# S02_Power_Converters.net
KiCad netlist of a schematic drawn in Altium Designer
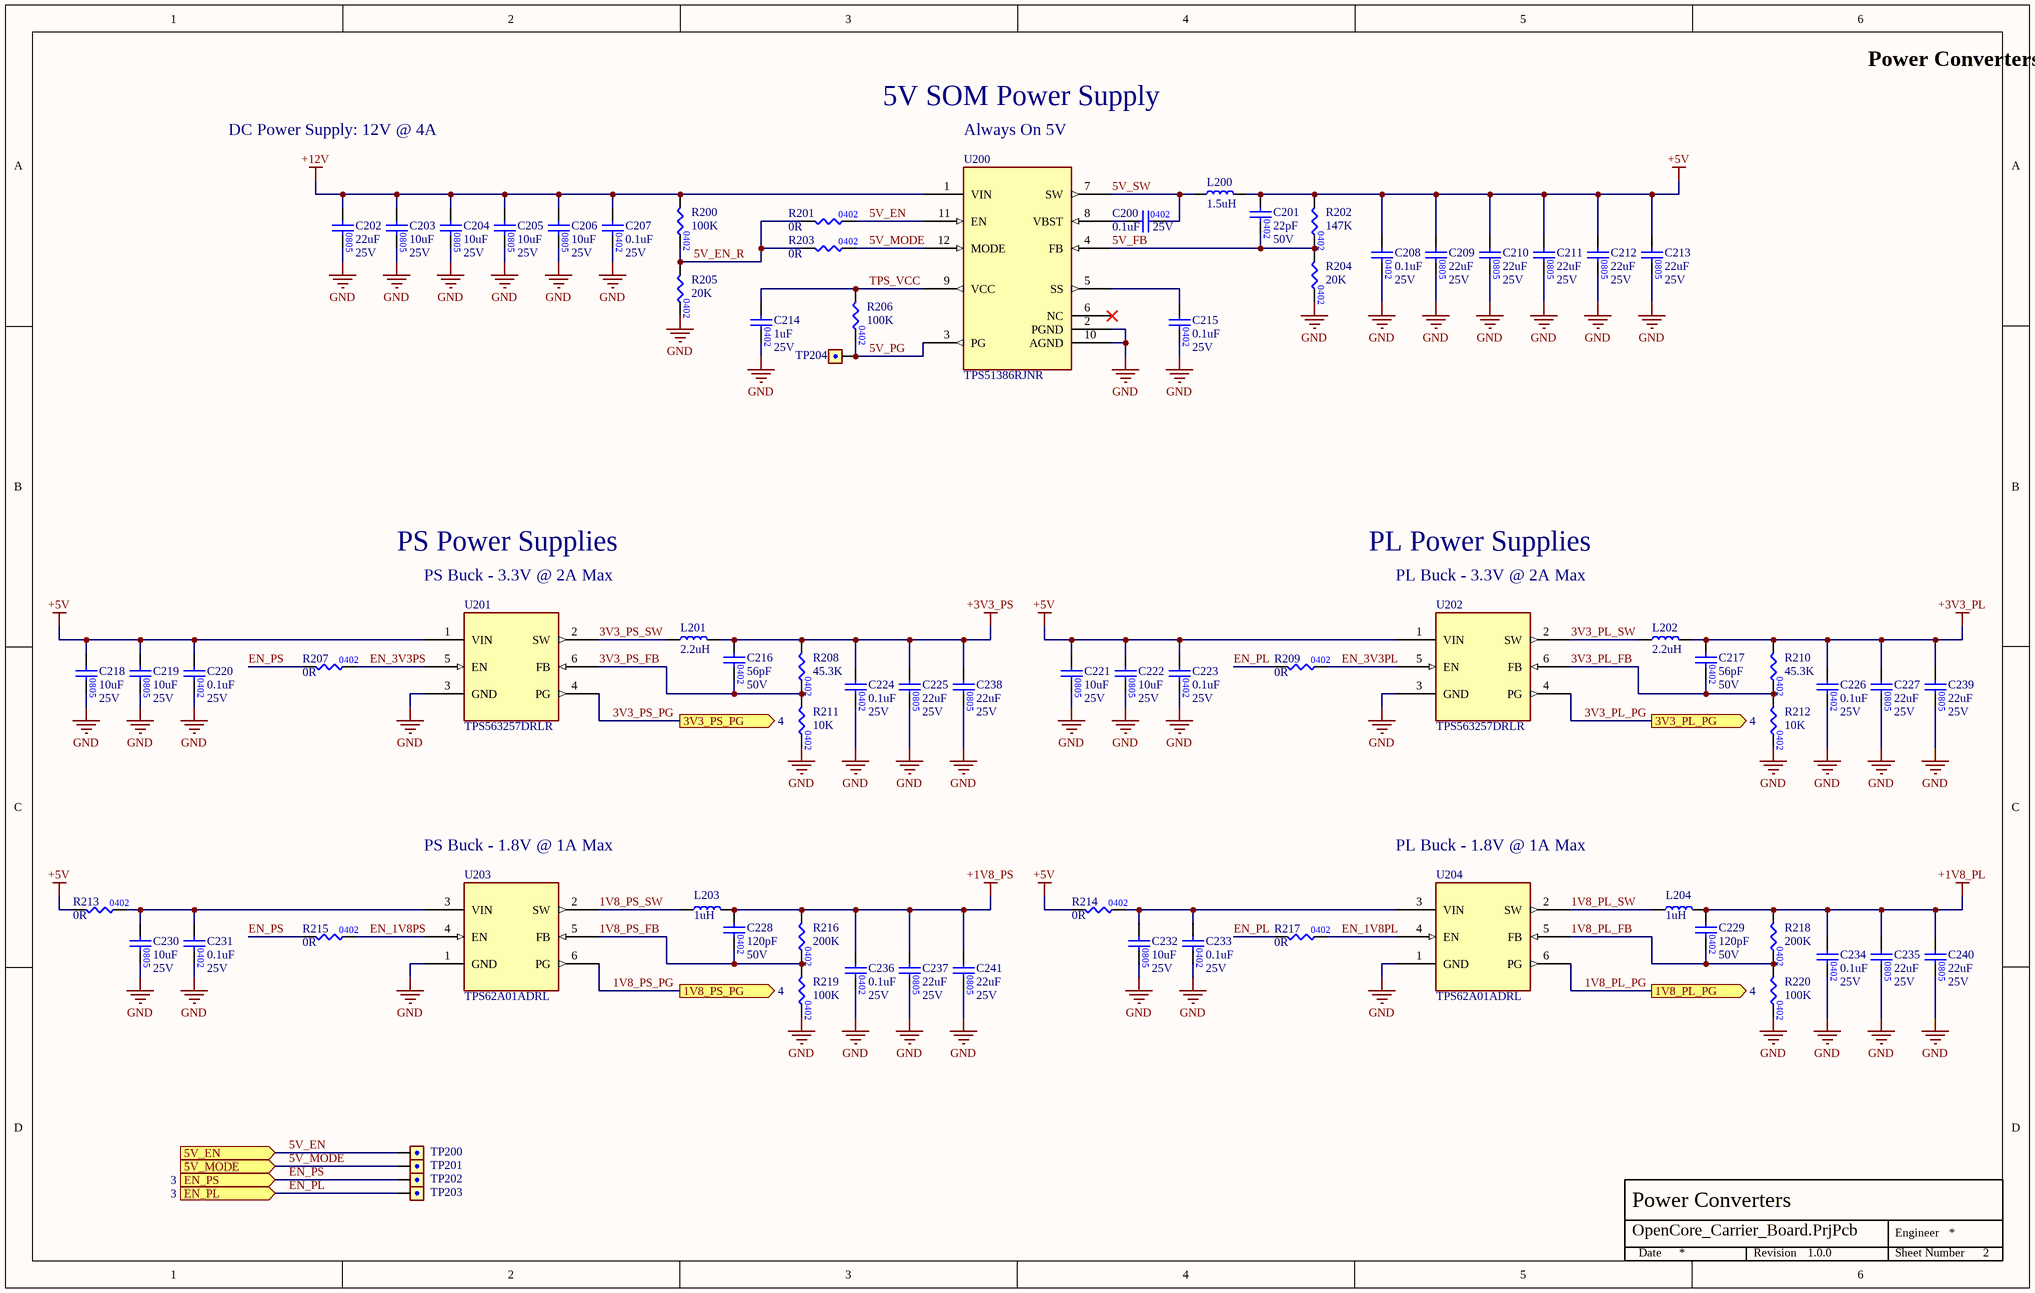
[diagram p0: S02_Power_Converters.SchDoc]

(export (version "E")
  (design (tool "Eeschema 10.0.6"))
  (components
    (comp (ref "C200")
      (value "0.1uF")
      (footprint "CAP0402")
      (description "CAP CER 0.1UF 25V X5R 0402")
      (fields
        (field (name "MANUFACTURER") "Samsung Electro-Mechanics")
        (field (name "TOLERANCE") "10%")
        (field (name "VOLTAGE RATING") "25V")
      )
      (libsource (lib "OpenCore_Sch_Lib") (part "CAP_CL05A104KA5NNNC"))
    )
    (comp (ref "C201")
      (value "22pF")
      (footprint "CAP0402")
      (description "CAP CER 22PF 50V C0G/NP0 0402")
      (fields
        (field (name "MANUFACTURER") "Samsung Electro-Mechanics")
        (field (name "TOLERANCE") "5%")
        (field (name "VOLTAGE RATING") "50V")
      )
      (libsource (lib "OpenCore_Sch_Lib") (part "CAP_CL05C220JB51PNC"))
    )
    (comp (ref "C202")
      (value "22uF")
      (footprint "CAP0805")
      (description "CAP CER 22UF 25V X5R 0805")
      (fields
        (field (name "MANUFACTURER") "Samsung Electro-Mechanics")
        (field (name "TOLERANCE") "20%")
        (field (name "VOLTAGE RATING") "25V")
      )
      (libsource (lib "OpenCore_Sch_Lib") (part "CAP_CL21A226MAYNNNE"))
    )
    (comp (ref "C203")
      (value "10uF")
      (footprint "CAP0805")
      (description "CAP CER 10UF 25V X5R 0805")
      (fields
        (field (name "MANUFACTURER") "Samsung Electro-Mechanics")
        (field (name "TOLERANCE") "10%")
        (field (name "VOLTAGE RATING") "25V")
      )
      (libsource (lib "OpenCore_Sch_Lib") (part "CAP_CL21A106KAYNNNE"))
    )
    (comp (ref "C204")
      (value "10uF")
      (footprint "CAP0805")
      (description "CAP CER 10UF 25V X5R 0805")
      (fields
        (field (name "MANUFACTURER") "Samsung Electro-Mechanics")
        (field (name "TOLERANCE") "10%")
        (field (name "VOLTAGE RATING") "25V")
      )
      (libsource (lib "OpenCore_Sch_Lib") (part "CAP_CL21A106KAYNNNE"))
    )
    (comp (ref "C205")
      (value "10uF")
      (footprint "CAP0805")
      (description "CAP CER 10UF 25V X5R 0805")
      (fields
        (field (name "MANUFACTURER") "Samsung Electro-Mechanics")
        (field (name "TOLERANCE") "10%")
        (field (name "VOLTAGE RATING") "25V")
      )
      (libsource (lib "OpenCore_Sch_Lib") (part "CAP_CL21A106KAYNNNE"))
    )
    (comp (ref "C206")
      (value "10uF")
      (footprint "CAP0805")
      (description "CAP CER 10UF 25V X5R 0805")
      (fields
        (field (name "MANUFACTURER") "Samsung Electro-Mechanics")
        (field (name "TOLERANCE") "10%")
        (field (name "VOLTAGE RATING") "25V")
      )
      (libsource (lib "OpenCore_Sch_Lib") (part "CAP_CL21A106KAYNNNE"))
    )
    (comp (ref "C207")
      (value "0.1uF")
      (footprint "CAP0402")
      (description "CAP CER 0.1UF 25V X5R 0402")
      (fields
        (field (name "MANUFACTURER") "Samsung Electro-Mechanics")
        (field (name "TOLERANCE") "10%")
        (field (name "VOLTAGE RATING") "25V")
      )
      (libsource (lib "OpenCore_Sch_Lib") (part "CAP_CL05A104KA5NNNC"))
    )
    (comp (ref "C208")
      (value "0.1uF")
      (footprint "CAP0402")
      (description "CAP CER 0.1UF 25V X5R 0402")
      (fields
        (field (name "MANUFACTURER") "Samsung Electro-Mechanics")
        (field (name "TOLERANCE") "10%")
        (field (name "VOLTAGE RATING") "25V")
      )
      (libsource (lib "OpenCore_Sch_Lib") (part "CAP_CL05A104KA5NNNC"))
    )
    (comp (ref "C209")
      (value "22uF")
      (footprint "CAP0805")
      (description "CAP CER 22UF 25V X5R 0805")
      (fields
        (field (name "MANUFACTURER") "Samsung Electro-Mechanics")
        (field (name "TOLERANCE") "20%")
        (field (name "VOLTAGE RATING") "25V")
      )
      (libsource (lib "OpenCore_Sch_Lib") (part "CAP_CL21A226MAYNNNE"))
    )
    (comp (ref "C210")
      (value "22uF")
      (footprint "CAP0805")
      (description "CAP CER 22UF 25V X5R 0805")
      (fields
        (field (name "MANUFACTURER") "Samsung Electro-Mechanics")
        (field (name "TOLERANCE") "20%")
        (field (name "VOLTAGE RATING") "25V")
      )
      (libsource (lib "OpenCore_Sch_Lib") (part "CAP_CL21A226MAYNNNE"))
    )
    (comp (ref "C211")
      (value "22uF")
      (footprint "CAP0805")
      (description "CAP CER 22UF 25V X5R 0805")
      (fields
        (field (name "MANUFACTURER") "Samsung Electro-Mechanics")
        (field (name "TOLERANCE") "20%")
        (field (name "VOLTAGE RATING") "25V")
      )
      (libsource (lib "OpenCore_Sch_Lib") (part "CAP_CL21A226MAYNNNE"))
    )
    (comp (ref "C212")
      (value "22uF")
      (footprint "CAP0805")
      (description "CAP CER 22UF 25V X5R 0805")
      (fields
        (field (name "MANUFACTURER") "Samsung Electro-Mechanics")
        (field (name "TOLERANCE") "20%")
        (field (name "VOLTAGE RATING") "25V")
      )
      (libsource (lib "OpenCore_Sch_Lib") (part "CAP_CL21A226MAYNNNE"))
    )
    (comp (ref "C213")
      (value "22uF")
      (footprint "CAP0805")
      (description "CAP CER 22UF 25V X5R 0805")
      (fields
        (field (name "MANUFACTURER") "Samsung Electro-Mechanics")
        (field (name "TOLERANCE") "20%")
        (field (name "VOLTAGE RATING") "25V")
      )
      (libsource (lib "OpenCore_Sch_Lib") (part "CAP_CL21A226MAYNNNE"))
    )
    (comp (ref "C214")
      (value "1uF")
      (footprint "CAP0402")
      (description "CAP CER 1UF 25V X5R 0603")
      (fields
        (field (name "MANUFACTURER") "Samsung Electro-Mechanics")
        (field (name "TOLERANCE") "10%")
        (field (name "VOLTAGE RATING") "25V")
      )
      (libsource (lib "OpenCore_Sch_Lib") (part "CAP_CL10A105KA8NNNC"))
    )
    (comp (ref "C215")
      (value "0.1uF")
      (footprint "CAP0402")
      (description "CAP CER 0.1UF 25V X5R 0402")
      (fields
        (field (name "MANUFACTURER") "Samsung Electro-Mechanics")
        (field (name "TOLERANCE") "10%")
        (field (name "VOLTAGE RATING") "25V")
      )
      (libsource (lib "OpenCore_Sch_Lib") (part "CAP_CL05A104KA5NNNC"))
    )
    (comp (ref "C216")
      (value "56pF")
      (footprint "CAP0402")
      (description "CAP CER 56PF 50V C0G/NPO 0402")
      (fields
        (field (name "MANUFACTURER") "YAGEO")
        (field (name "TOLERANCE") "5%")
        (field (name "VOLTAGE RATING") "50V")
      )
      (libsource (lib "OpenCore_Sch_Lib") (part "CAP_CC0402JRNPO9BN560"))
    )
    (comp (ref "C217")
      (value "56pF")
      (footprint "CAP0402")
      (description "CAP CER 56PF 50V C0G/NPO 0402")
      (fields
        (field (name "MANUFACTURER") "YAGEO")
        (field (name "TOLERANCE") "5%")
        (field (name "VOLTAGE RATING") "50V")
      )
      (libsource (lib "OpenCore_Sch_Lib") (part "CAP_CC0402JRNPO9BN560"))
    )
    (comp (ref "C218")
      (value "10uF")
      (footprint "CAP0805")
      (description "CAP CER 10UF 25V X5R 0805")
      (fields
        (field (name "MANUFACTURER") "Samsung Electro-Mechanics")
        (field (name "TOLERANCE") "10%")
        (field (name "VOLTAGE RATING") "25V")
      )
      (libsource (lib "OpenCore_Sch_Lib") (part "CAP_CL21A106KAYNNNE"))
    )
    (comp (ref "C219")
      (value "10uF")
      (footprint "CAP0805")
      (description "CAP CER 10UF 25V X5R 0805")
      (fields
        (field (name "MANUFACTURER") "Samsung Electro-Mechanics")
        (field (name "TOLERANCE") "10%")
        (field (name "VOLTAGE RATING") "25V")
      )
      (libsource (lib "OpenCore_Sch_Lib") (part "CAP_CL21A106KAYNNNE"))
    )
    (comp (ref "C220")
      (value "0.1uF")
      (footprint "CAP0402")
      (description "CAP CER 0.1UF 25V X5R 0402")
      (fields
        (field (name "MANUFACTURER") "Samsung Electro-Mechanics")
        (field (name "TOLERANCE") "10%")
        (field (name "VOLTAGE RATING") "25V")
      )
      (libsource (lib "OpenCore_Sch_Lib") (part "CAP_CL05A104KA5NNNC"))
    )
    (comp (ref "C221")
      (value "10uF")
      (footprint "CAP0805")
      (description "CAP CER 10UF 25V X5R 0805")
      (fields
        (field (name "MANUFACTURER") "Samsung Electro-Mechanics")
        (field (name "TOLERANCE") "10%")
        (field (name "VOLTAGE RATING") "25V")
      )
      (libsource (lib "OpenCore_Sch_Lib") (part "CAP_CL21A106KAYNNNE"))
    )
    (comp (ref "C222")
      (value "10uF")
      (footprint "CAP0805")
      (description "CAP CER 10UF 25V X5R 0805")
      (fields
        (field (name "MANUFACTURER") "Samsung Electro-Mechanics")
        (field (name "TOLERANCE") "10%")
        (field (name "VOLTAGE RATING") "25V")
      )
      (libsource (lib "OpenCore_Sch_Lib") (part "CAP_CL21A106KAYNNNE"))
    )
    (comp (ref "C223")
      (value "0.1uF")
      (footprint "CAP0402")
      (description "CAP CER 0.1UF 25V X5R 0402")
      (fields
        (field (name "MANUFACTURER") "Samsung Electro-Mechanics")
        (field (name "TOLERANCE") "10%")
        (field (name "VOLTAGE RATING") "25V")
      )
      (libsource (lib "OpenCore_Sch_Lib") (part "CAP_CL05A104KA5NNNC"))
    )
    (comp (ref "C224")
      (value "0.1uF")
      (footprint "CAP0402")
      (description "CAP CER 0.1UF 25V X5R 0402")
      (fields
        (field (name "MANUFACTURER") "Samsung Electro-Mechanics")
        (field (name "TOLERANCE") "10%")
        (field (name "VOLTAGE RATING") "25V")
      )
      (libsource (lib "OpenCore_Sch_Lib") (part "CAP_CL05A104KA5NNNC"))
    )
    (comp (ref "C225")
      (value "22uF")
      (footprint "CAP0805")
      (description "CAP CER 22UF 25V X5R 0805")
      (fields
        (field (name "MANUFACTURER") "Samsung Electro-Mechanics")
        (field (name "TOLERANCE") "20%")
        (field (name "VOLTAGE RATING") "25V")
      )
      (libsource (lib "OpenCore_Sch_Lib") (part "CAP_CL21A226MAYNNNE"))
    )
    (comp (ref "C226")
      (value "0.1uF")
      (footprint "CAP0402")
      (description "CAP CER 0.1UF 25V X5R 0402")
      (fields
        (field (name "MANUFACTURER") "Samsung Electro-Mechanics")
        (field (name "TOLERANCE") "10%")
        (field (name "VOLTAGE RATING") "25V")
      )
      (libsource (lib "OpenCore_Sch_Lib") (part "CAP_CL05A104KA5NNNC"))
    )
    (comp (ref "C227")
      (value "22uF")
      (footprint "CAP0805")
      (description "CAP CER 22UF 25V X5R 0805")
      (fields
        (field (name "MANUFACTURER") "Samsung Electro-Mechanics")
        (field (name "TOLERANCE") "20%")
        (field (name "VOLTAGE RATING") "25V")
      )
      (libsource (lib "OpenCore_Sch_Lib") (part "CAP_CL21A226MAYNNNE"))
    )
    (comp (ref "C228")
      (value "120pF")
      (footprint "CAP0402")
      (description "CAP CER 120PF 50V C0G/NP0 0402")
      (fields
        (field (name "MANUFACTURER") "Samsung Electro-Mechanics")
        (field (name "TOLERANCE") "5%")
        (field (name "VOLTAGE RATING") "50V")
      )
      (libsource (lib "OpenCore_Sch_Lib") (part "CAP_CL05C121JB51PNC"))
    )
    (comp (ref "C229")
      (value "120pF")
      (footprint "CAP0402")
      (description "CAP CER 120PF 50V C0G/NP0 0402")
      (fields
        (field (name "MANUFACTURER") "Samsung Electro-Mechanics")
        (field (name "TOLERANCE") "5%")
        (field (name "VOLTAGE RATING") "50V")
      )
      (libsource (lib "OpenCore_Sch_Lib") (part "CAP_CL05C121JB51PNC"))
    )
    (comp (ref "C230")
      (value "10uF")
      (footprint "CAP0805")
      (description "CAP CER 10UF 25V X5R 0805")
      (fields
        (field (name "MANUFACTURER") "Samsung Electro-Mechanics")
        (field (name "TOLERANCE") "10%")
        (field (name "VOLTAGE RATING") "25V")
      )
      (libsource (lib "OpenCore_Sch_Lib") (part "CAP_CL21A106KAYNNNE"))
    )
    (comp (ref "C231")
      (value "0.1uF")
      (footprint "CAP0402")
      (description "CAP CER 0.1UF 25V X5R 0402")
      (fields
        (field (name "MANUFACTURER") "Samsung Electro-Mechanics")
        (field (name "TOLERANCE") "10%")
        (field (name "VOLTAGE RATING") "25V")
      )
      (libsource (lib "OpenCore_Sch_Lib") (part "CAP_CL05A104KA5NNNC"))
    )
    (comp (ref "C232")
      (value "10uF")
      (footprint "CAP0805")
      (description "CAP CER 10UF 25V X5R 0805")
      (fields
        (field (name "MANUFACTURER") "Samsung Electro-Mechanics")
        (field (name "TOLERANCE") "10%")
        (field (name "VOLTAGE RATING") "25V")
      )
      (libsource (lib "OpenCore_Sch_Lib") (part "CAP_CL21A106KAYNNNE"))
    )
    (comp (ref "C233")
      (value "0.1uF")
      (footprint "CAP0402")
      (description "CAP CER 0.1UF 25V X5R 0402")
      (fields
        (field (name "MANUFACTURER") "Samsung Electro-Mechanics")
        (field (name "TOLERANCE") "10%")
        (field (name "VOLTAGE RATING") "25V")
      )
      (libsource (lib "OpenCore_Sch_Lib") (part "CAP_CL05A104KA5NNNC"))
    )
    (comp (ref "C234")
      (value "0.1uF")
      (footprint "CAP0402")
      (description "CAP CER 0.1UF 25V X5R 0402")
      (fields
        (field (name "MANUFACTURER") "Samsung Electro-Mechanics")
        (field (name "TOLERANCE") "10%")
        (field (name "VOLTAGE RATING") "25V")
      )
      (libsource (lib "OpenCore_Sch_Lib") (part "CAP_CL05A104KA5NNNC"))
    )
    (comp (ref "C235")
      (value "22uF")
      (footprint "CAP0805")
      (description "CAP CER 22UF 25V X5R 0805")
      (fields
        (field (name "MANUFACTURER") "Samsung Electro-Mechanics")
        (field (name "TOLERANCE") "20%")
        (field (name "VOLTAGE RATING") "25V")
      )
      (libsource (lib "OpenCore_Sch_Lib") (part "CAP_CL21A226MAYNNNE"))
    )
    (comp (ref "C236")
      (value "0.1uF")
      (footprint "CAP0402")
      (description "CAP CER 0.1UF 25V X5R 0402")
      (fields
        (field (name "MANUFACTURER") "Samsung Electro-Mechanics")
        (field (name "TOLERANCE") "10%")
        (field (name "VOLTAGE RATING") "25V")
      )
      (libsource (lib "OpenCore_Sch_Lib") (part "CAP_CL05A104KA5NNNC"))
    )
    (comp (ref "C237")
      (value "22uF")
      (footprint "CAP0805")
      (description "CAP CER 22UF 25V X5R 0805")
      (fields
        (field (name "MANUFACTURER") "Samsung Electro-Mechanics")
        (field (name "TOLERANCE") "20%")
        (field (name "VOLTAGE RATING") "25V")
      )
      (libsource (lib "OpenCore_Sch_Lib") (part "CAP_CL21A226MAYNNNE"))
    )
    (comp (ref "C238")
      (value "22uF")
      (footprint "CAP0805")
      (description "CAP CER 22UF 25V X5R 0805")
      (fields
        (field (name "MANUFACTURER") "Samsung Electro-Mechanics")
        (field (name "TOLERANCE") "20%")
        (field (name "VOLTAGE RATING") "25V")
      )
      (libsource (lib "OpenCore_Sch_Lib") (part "CAP_CL21A226MAYNNNE"))
    )
    (comp (ref "C239")
      (value "22uF")
      (footprint "CAP0805")
      (description "CAP CER 22UF 25V X5R 0805")
      (fields
        (field (name "MANUFACTURER") "Samsung Electro-Mechanics")
        (field (name "TOLERANCE") "20%")
        (field (name "VOLTAGE RATING") "25V")
      )
      (libsource (lib "OpenCore_Sch_Lib") (part "CAP_CL21A226MAYNNNE"))
    )
    (comp (ref "C240")
      (value "22uF")
      (footprint "CAP0805")
      (description "CAP CER 22UF 25V X5R 0805")
      (fields
        (field (name "MANUFACTURER") "Samsung Electro-Mechanics")
        (field (name "TOLERANCE") "20%")
        (field (name "VOLTAGE RATING") "25V")
      )
      (libsource (lib "OpenCore_Sch_Lib") (part "CAP_CL21A226MAYNNNE"))
    )
    (comp (ref "C241")
      (value "22uF")
      (footprint "CAP0805")
      (description "CAP CER 22UF 25V X5R 0805")
      (fields
        (field (name "MANUFACTURER") "Samsung Electro-Mechanics")
        (field (name "TOLERANCE") "20%")
        (field (name "VOLTAGE RATING") "25V")
      )
      (libsource (lib "OpenCore_Sch_Lib") (part "CAP_CL21A226MAYNNNE"))
    )
    (comp (ref "L200")
      (value "IHLP5050CEER1R5M01")
      (footprint "IHLP5050CEER1R5M01")
      (description "FIXED IND 1.5UH 19A 5.5 MOHM SMD")
      (fields
        (field (name "MANUFACTURER") "Vishay Dale")
        (field (name "TOLERANCE") "20%")
        (field (name "INDUCTANCE") "1.5uH")
      )
      (libsource (lib "OpenCore_Sch_Lib") (part "IND_IHLP5050CEER1R5M01"))
    )
    (comp (ref "L201")
      (value "SDCHA1V6045-2R2-R")
      (footprint "SDCHA1V6045-2R2-R")
      (description "IND SMD POWER 2.2UH 6.0A")
      (fields
        (field (name "MANUFACTURER") "Eaton - Electronics Division")
        (field (name "TOLERANCE") "20%")
        (field (name "INDUCTANCE") "2.2uH")
      )
      (libsource (lib "OpenCore_Sch_Lib") (part "IND_SDCHA1V6045-2R2-R"))
    )
    (comp (ref "L202")
      (value "SDCHA1V6045-2R2-R")
      (footprint "SDCHA1V6045-2R2-R")
      (description "IND SMD POWER 2.2UH 6.0A")
      (fields
        (field (name "MANUFACTURER") "Eaton - Electronics Division")
        (field (name "TOLERANCE") "20%")
        (field (name "INDUCTANCE") "2.2uH")
      )
      (libsource (lib "OpenCore_Sch_Lib") (part "IND_SDCHA1V6045-2R2-R"))
    )
    (comp (ref "L203")
      (value "DFE252012F-1R0M")
      (footprint "IND_2520")
      (description "FIXED IND 1UH 3.3A 0.04OHM SMD")
      (fields
        (field (name "MANUFACTURER") "Murata Electronics")
        (field (name "TOLERANCE") "20%")
        (field (name "INDUCTANCE") "1uH")
      )
      (libsource (lib "OpenCore_Sch_Lib") (part "IND_DFE252012F-1R0M"))
    )
    (comp (ref "L204")
      (value "DFE252012F-1R0M")
      (footprint "IND_2520")
      (description "FIXED IND 1UH 3.3A 0.04OHM SMD")
      (fields
        (field (name "MANUFACTURER") "Murata Electronics")
        (field (name "TOLERANCE") "20%")
        (field (name "INDUCTANCE") "1uH")
      )
      (libsource (lib "OpenCore_Sch_Lib") (part "IND_DFE252012F-1R0M"))
    )
    (comp (ref "R200")
      (value "RES_0402")
      (footprint "RES0402")
      (description "RES 100K OHM 1% 1/16W 0402")
      (fields
        (field (name "MANUFACTURER") "YAGEO")
        (field (name "MANUFACTURER PART NUMBER") "RC0402FR-07100KL")
        (field (name "RESISTANCE") "100K")
      )
      (libsource (lib "OpenCore_Sch_Lib") (part ".RES_RC0402FR-07100KL"))
    )
    (comp (ref "R201")
      (value "RES_0402")
      (footprint "RES0402")
      (description "RES 0 OHM JUMPER 1/16W 0402")
      (fields
        (field (name "MANUFACTURER") "YAGEO")
        (field (name "MANUFACTURER PART NUMBER") "RC0402JR-070RL")
        (field (name "RESISTANCE") "0R")
      )
      (libsource (lib "OpenCore_Sch_Lib") (part ".RES_RC0402JR-070RL"))
    )
    (comp (ref "R202")
      (value "RES_0402")
      (footprint "RES0402")
      (description "RES 147K OHM 1% 1/16W 0402")
      (fields
        (field (name "MANUFACTURER") "YAGEO")
        (field (name "MANUFACTURER PART NUMBER") "RC0402FR-07147KL")
        (field (name "RESISTANCE") "147K")
      )
      (libsource (lib "OpenCore_Sch_Lib") (part ".RES_RC0402FR-07147KL"))
    )
    (comp (ref "R203")
      (value "RES_0402")
      (footprint "RES0402")
      (description "RES 0 OHM JUMPER 1/16W 0402")
      (fields
        (field (name "MANUFACTURER") "YAGEO")
        (field (name "MANUFACTURER PART NUMBER") "RC0402JR-070RL")
        (field (name "RESISTANCE") "0R")
      )
      (libsource (lib "OpenCore_Sch_Lib") (part ".RES_RC0402JR-070RL"))
    )
    (comp (ref "R204")
      (value "RES_0402")
      (footprint "RES0402")
      (description "RES 20K OHM 1% 1/16W 0402")
      (fields
        (field (name "MANUFACTURER") "YAGEO")
        (field (name "MANUFACTURER PART NUMBER") "RC0402FR-0720KL")
        (field (name "RESISTANCE") "20K")
      )
      (libsource (lib "OpenCore_Sch_Lib") (part ".RES_RC0402FR-0720KL"))
    )
    (comp (ref "R205")
      (value "RES_0402")
      (footprint "RES0402")
      (description "RES 20K OHM 1% 1/16W 0402")
      (fields
        (field (name "MANUFACTURER") "YAGEO")
        (field (name "MANUFACTURER PART NUMBER") "RC0402FR-0720KL")
        (field (name "RESISTANCE") "20K")
      )
      (libsource (lib "OpenCore_Sch_Lib") (part ".RES_RC0402FR-0720KL"))
    )
    (comp (ref "R206")
      (value "RES_0402")
      (footprint "RES0402")
      (description "RES 100K OHM 1% 1/16W 0402")
      (fields
        (field (name "MANUFACTURER") "YAGEO")
        (field (name "MANUFACTURER PART NUMBER") "RC0402FR-07100KL")
        (field (name "RESISTANCE") "100K")
      )
      (libsource (lib "OpenCore_Sch_Lib") (part ".RES_RC0402FR-07100KL"))
    )
    (comp (ref "R207")
      (value "RES_0402")
      (footprint "RES0402")
      (description "RES 0 OHM JUMPER 1/16W 0402")
      (fields
        (field (name "MANUFACTURER") "YAGEO")
        (field (name "MANUFACTURER PART NUMBER") "RC0402JR-070RL")
        (field (name "RESISTANCE") "0R")
      )
      (libsource (lib "OpenCore_Sch_Lib") (part ".RES_RC0402JR-070RL"))
    )
    (comp (ref "R208")
      (value "RES_0402")
      (footprint "RES0402")
      (description "RES 45.3K OHM 1% 1/16W 0402")
      (fields
        (field (name "MANUFACTURER") "YAGEO")
        (field (name "MANUFACTURER PART NUMBER") "RC0402FR-0745K3L")
        (field (name "RESISTANCE") "45.3K")
      )
      (libsource (lib "OpenCore_Sch_Lib") (part ".RES_RC0402FR-0745K3L"))
    )
    (comp (ref "R209")
      (value "RES_0402")
      (footprint "RES0402")
      (description "RES 0 OHM JUMPER 1/16W 0402")
      (fields
        (field (name "MANUFACTURER") "YAGEO")
        (field (name "MANUFACTURER PART NUMBER") "RC0402JR-070RL")
        (field (name "RESISTANCE") "0R")
      )
      (libsource (lib "OpenCore_Sch_Lib") (part ".RES_RC0402JR-070RL"))
    )
    (comp (ref "R210")
      (value "RES_0402")
      (footprint "RES0402")
      (description "RES 45.3K OHM 1% 1/16W 0402")
      (fields
        (field (name "MANUFACTURER") "YAGEO")
        (field (name "MANUFACTURER PART NUMBER") "RC0402FR-0745K3L")
        (field (name "RESISTANCE") "45.3K")
      )
      (libsource (lib "OpenCore_Sch_Lib") (part ".RES_RC0402FR-0745K3L"))
    )
    (comp (ref "R211")
      (value "RES_0402")
      (footprint "RES0402")
      (description "RES 10K OHM 1% 1/16W 0402")
      (fields
        (field (name "MANUFACTURER") "YAGEO")
        (field (name "MANUFACTURER PART NUMBER") "RC0402FR-0710KL")
        (field (name "RESISTANCE") "10K")
      )
      (libsource (lib "OpenCore_Sch_Lib") (part ".RES_RC0402FR-0710KL"))
    )
    (comp (ref "R212")
      (value "RES_0402")
      (footprint "RES0402")
      (description "RES 10K OHM 1% 1/16W 0402")
      (fields
        (field (name "MANUFACTURER") "YAGEO")
        (field (name "MANUFACTURER PART NUMBER") "RC0402FR-0710KL")
        (field (name "RESISTANCE") "10K")
      )
      (libsource (lib "OpenCore_Sch_Lib") (part ".RES_RC0402FR-0710KL"))
    )
    (comp (ref "R213")
      (value "RES_0402")
      (footprint "RES0402")
      (description "RES 0 OHM JUMPER 1/16W 0402")
      (fields
        (field (name "MANUFACTURER") "YAGEO")
        (field (name "MANUFACTURER PART NUMBER") "RC0402JR-070RL")
        (field (name "RESISTANCE") "0R")
      )
      (libsource (lib "OpenCore_Sch_Lib") (part ".RES_RC0402JR-070RL"))
    )
    (comp (ref "R214")
      (value "RES_0402")
      (footprint "RES0402")
      (description "RES 0 OHM JUMPER 1/16W 0402")
      (fields
        (field (name "MANUFACTURER") "YAGEO")
        (field (name "MANUFACTURER PART NUMBER") "RC0402JR-070RL")
        (field (name "RESISTANCE") "0R")
      )
      (libsource (lib "OpenCore_Sch_Lib") (part ".RES_RC0402JR-070RL"))
    )
    (comp (ref "R215")
      (value "RES_0402")
      (footprint "RES0402")
      (description "RES 0 OHM JUMPER 1/16W 0402")
      (fields
        (field (name "MANUFACTURER") "YAGEO")
        (field (name "MANUFACTURER PART NUMBER") "RC0402JR-070RL")
        (field (name "RESISTANCE") "0R")
      )
      (libsource (lib "OpenCore_Sch_Lib") (part ".RES_RC0402JR-070RL"))
    )
    (comp (ref "R216")
      (value "RES_0402")
      (footprint "RES0402")
      (description "RES 200K OHM 1% 1/16W 0402")
      (fields
        (field (name "MANUFACTURER") "YAGEO")
        (field (name "MANUFACTURER PART NUMBER") "RC0402FR-07200KL")
        (field (name "RESISTANCE") "200K")
      )
      (libsource (lib "OpenCore_Sch_Lib") (part ".RES_RC0402FR-07200KL"))
    )
    (comp (ref "R217")
      (value "RES_0402")
      (footprint "RES0402")
      (description "RES 0 OHM JUMPER 1/16W 0402")
      (fields
        (field (name "MANUFACTURER") "YAGEO")
        (field (name "MANUFACTURER PART NUMBER") "RC0402JR-070RL")
        (field (name "RESISTANCE") "0R")
      )
      (libsource (lib "OpenCore_Sch_Lib") (part ".RES_RC0402JR-070RL"))
    )
    (comp (ref "R218")
      (value "RES_0402")
      (footprint "RES0402")
      (description "RES 200K OHM 1% 1/16W 0402")
      (fields
        (field (name "MANUFACTURER") "YAGEO")
        (field (name "MANUFACTURER PART NUMBER") "RC0402FR-07200KL")
        (field (name "RESISTANCE") "200K")
      )
      (libsource (lib "OpenCore_Sch_Lib") (part ".RES_RC0402FR-07200KL"))
    )
    (comp (ref "R219")
      (value "RES_0402")
      (footprint "RES0402")
      (description "RES 100K OHM 1% 1/16W 0402")
      (fields
        (field (name "MANUFACTURER") "YAGEO")
        (field (name "MANUFACTURER PART NUMBER") "RC0402FR-07100KL")
        (field (name "RESISTANCE") "100K")
      )
      (libsource (lib "OpenCore_Sch_Lib") (part ".RES_RC0402FR-07100KL"))
    )
    (comp (ref "R220")
      (value "RES_0402")
      (footprint "RES0402")
      (description "RES 100K OHM 1% 1/16W 0402")
      (fields
        (field (name "MANUFACTURER") "YAGEO")
        (field (name "MANUFACTURER PART NUMBER") "RC0402FR-07100KL")
        (field (name "RESISTANCE") "100K")
      )
      (libsource (lib "OpenCore_Sch_Lib") (part ".RES_RC0402FR-07100KL"))
    )
    (comp (ref "TP200")
      (value "1mm Round Pad Testpoint")
      (footprint "TP_1MM")
      (libsource (lib "OpenCore_Sch_Lib") (part "TP_1MM"))
    )
    (comp (ref "TP201")
      (value "1mm Round Pad Testpoint")
      (footprint "TP_1MM")
      (libsource (lib "OpenCore_Sch_Lib") (part "TP_1MM"))
    )
    (comp (ref "TP202")
      (value "1mm Round Pad Testpoint")
      (footprint "TP_1MM")
      (libsource (lib "OpenCore_Sch_Lib") (part "TP_1MM"))
    )
    (comp (ref "TP203")
      (value "1mm Round Pad Testpoint")
      (footprint "TP_1MM")
      (libsource (lib "OpenCore_Sch_Lib") (part "TP_1MM"))
    )
    (comp (ref "TP204")
      (value "1mm Round Pad Testpoint")
      (footprint "TP_1MM")
      (libsource (lib "") (part "TP_1MM_1"))
    )
    (comp (ref "U200")
      (value "TPS51386RJNR")
      (footprint "TI_RJN0012A_POWERVQFN12")
      (description "IC REG BUCK ADJ 8A 12-PowerVFQFN")
      (fields (field (name "MANUFACTURER") "Texas Instruments"))
      (libsource (lib "OpenCore_Sch_Lib") (part "TPS51386RJNR"))
    )
    (comp (ref "U201")
      (value "TPS563257DRLR")
      (footprint "TI_SOT6_DRL0006A")
      (description "IC REG BUCK ADJ 3A SOT563")
      (libsource (lib "OpenCore_Sch_Lib") (part "TPS563257DRLR"))
    )
    (comp (ref "U202")
      (value "TPS563257DRLR")
      (footprint "TI_SOT6_DRL0006A")
      (description "IC REG BUCK ADJ 3A SOT563")
      (libsource (lib "OpenCore_Sch_Lib") (part "TPS563257DRLR"))
    )
    (comp (ref "U203")
      (value "TPS62A01ADRL")
      (footprint "TI_SOT6_DRL0006A")
      (description "IC REG BUCK ADJ 1A SOT5X3")
      (fields
        (field (name "MANUFACTURER") "Texas Instruments")
        (field (name "MANUFACTURER PART NUMBER") "TLV62568ADRLR")
      )
      (libsource (lib "OpenCore_Sch_Lib") (part "TPS62A01ADRL"))
    )
    (comp (ref "U204")
      (value "TPS62A01ADRL")
      (footprint "TI_SOT6_DRL0006A")
      (description "IC REG BUCK ADJ 1A SOT5X3")
      (fields
        (field (name "MANUFACTURER") "Texas Instruments")
        (field (name "MANUFACTURER PART NUMBER") "TLV62568ADRLR")
      )
      (libsource (lib "OpenCore_Sch_Lib") (part "TPS62A01ADRL"))
    )
  )
  (nets
    (net (code "1") (name "+1V8_PL") (class "Default")
      (node (ref "C229") (pin "1") (pinfunction "1_1") (pintype "passive"))
      (node (ref "C234") (pin "1") (pinfunction "1_1") (pintype "passive"))
      (node (ref "C235") (pin "1") (pinfunction "1_1") (pintype "passive"))
      (node (ref "C240") (pin "1") (pinfunction "1_1") (pintype "passive"))
      (node (ref "L204") (pin "2") (pinfunction "2_2") (pintype "passive"))
      (node (ref "R218") (pin "1") (pinfunction "1_1") (pintype "passive"))
    )
    (net (code "2") (name "+1V8_PS") (class "Default")
      (node (ref "C228") (pin "1") (pinfunction "1_1") (pintype "passive"))
      (node (ref "C236") (pin "1") (pinfunction "1_1") (pintype "passive"))
      (node (ref "C237") (pin "1") (pinfunction "1_1") (pintype "passive"))
      (node (ref "C241") (pin "1") (pinfunction "1_1") (pintype "passive"))
      (node (ref "L203") (pin "2") (pinfunction "2_2") (pintype "passive"))
      (node (ref "R216") (pin "1") (pinfunction "1_1") (pintype "passive"))
    )
    (net (code "3") (name "+3V3_PL") (class "Default")
      (node (ref "C217") (pin "1") (pinfunction "1_1") (pintype "passive"))
      (node (ref "C226") (pin "1") (pinfunction "1_1") (pintype "passive"))
      (node (ref "C227") (pin "1") (pinfunction "1_1") (pintype "passive"))
      (node (ref "C239") (pin "1") (pinfunction "1_1") (pintype "passive"))
      (node (ref "L202") (pin "2") (pinfunction "2_2") (pintype "passive"))
      (node (ref "R210") (pin "1") (pinfunction "1_1") (pintype "passive"))
    )
    (net (code "4") (name "+3V3_PS") (class "Default")
      (node (ref "C216") (pin "1") (pinfunction "1_1") (pintype "passive"))
      (node (ref "C224") (pin "1") (pinfunction "1_1") (pintype "passive"))
      (node (ref "C225") (pin "1") (pinfunction "1_1") (pintype "passive"))
      (node (ref "C238") (pin "1") (pinfunction "1_1") (pintype "passive"))
      (node (ref "L201") (pin "2") (pinfunction "2_2") (pintype "passive"))
      (node (ref "R208") (pin "1") (pinfunction "1_1") (pintype "passive"))
    )
    (net (code "5") (name "+5V") (class "Default")
      (node (ref "C201") (pin "1") (pinfunction "1_1") (pintype "passive"))
      (node (ref "C208") (pin "1") (pinfunction "1_1") (pintype "passive"))
      (node (ref "C209") (pin "1") (pinfunction "1_1") (pintype "passive"))
      (node (ref "C210") (pin "1") (pinfunction "1_1") (pintype "passive"))
      (node (ref "C211") (pin "1") (pinfunction "1_1") (pintype "passive"))
      (node (ref "C212") (pin "1") (pinfunction "1_1") (pintype "passive"))
      (node (ref "C213") (pin "1") (pinfunction "1_1") (pintype "passive"))
      (node (ref "C218") (pin "1") (pinfunction "1_1") (pintype "passive"))
      (node (ref "C219") (pin "1") (pinfunction "1_1") (pintype "passive"))
      (node (ref "C220") (pin "1") (pinfunction "1_1") (pintype "passive"))
      (node (ref "C221") (pin "1") (pinfunction "1_1") (pintype "passive"))
      (node (ref "C222") (pin "1") (pinfunction "1_1") (pintype "passive"))
      (node (ref "C223") (pin "1") (pinfunction "1_1") (pintype "passive"))
      (node (ref "L200") (pin "2") (pinfunction "2_2") (pintype "passive"))
      (node (ref "R202") (pin "1") (pinfunction "1_1") (pintype "passive"))
      (node (ref "R213") (pin "1") (pinfunction "1_1") (pintype "passive"))
      (node (ref "R214") (pin "1") (pinfunction "1_1") (pintype "passive"))
      (node (ref "U201") (pin "1") (pinfunction "VIN_1") (pintype "power_in"))
      (node (ref "U202") (pin "1") (pinfunction "VIN_1") (pintype "power_in"))
    )
    (net (code "6") (name "+12V") (class "Default")
      (node (ref "C202") (pin "1") (pinfunction "1_1") (pintype "passive"))
      (node (ref "C203") (pin "1") (pinfunction "1_1") (pintype "passive"))
      (node (ref "C204") (pin "1") (pinfunction "1_1") (pintype "passive"))
      (node (ref "C205") (pin "1") (pinfunction "1_1") (pintype "passive"))
      (node (ref "C206") (pin "1") (pinfunction "1_1") (pintype "passive"))
      (node (ref "C207") (pin "1") (pinfunction "1_1") (pintype "passive"))
      (node (ref "R200") (pin "1") (pinfunction "1_1") (pintype "passive"))
      (node (ref "U200") (pin "1") (pinfunction "VIN_1") (pintype "power_in"))
    )
    (net (code "7") (name "/1V8_PL_FB") (class "Default")
      (node (ref "C229") (pin "2") (pinfunction "2_2") (pintype "passive"))
      (node (ref "R218") (pin "2") (pinfunction "2_2") (pintype "passive"))
      (node (ref "R220") (pin "1") (pinfunction "1_1") (pintype "passive"))
      (node (ref "U204") (pin "5") (pinfunction "FB_5") (pintype "input"))
    )
    (net (code "8") (name "/1V8_PL_PG") (class "Default")
      (node (ref "U204") (pin "6") (pinfunction "PG_6") (pintype "output"))
    )
    (net (code "9") (name "/1V8_PL_SW") (class "Default")
      (node (ref "L204") (pin "1") (pinfunction "1_1") (pintype "passive"))
      (node (ref "U204") (pin "2") (pinfunction "SW_2") (pintype "output"))
    )
    (net (code "10") (name "/1V8_PS_FB") (class "Default")
      (node (ref "C228") (pin "2") (pinfunction "2_2") (pintype "passive"))
      (node (ref "R216") (pin "2") (pinfunction "2_2") (pintype "passive"))
      (node (ref "R219") (pin "1") (pinfunction "1_1") (pintype "passive"))
      (node (ref "U203") (pin "5") (pinfunction "FB_5") (pintype "input"))
    )
    (net (code "11") (name "/1V8_PS_PG") (class "Default")
      (node (ref "U203") (pin "6") (pinfunction "PG_6") (pintype "output"))
    )
    (net (code "12") (name "/1V8_PS_SW") (class "Default")
      (node (ref "L203") (pin "1") (pinfunction "1_1") (pintype "passive"))
      (node (ref "U203") (pin "2") (pinfunction "SW_2") (pintype "output"))
    )
    (net (code "13") (name "/3V3_PL_FB") (class "Default")
      (node (ref "C217") (pin "2") (pinfunction "2_2") (pintype "passive"))
      (node (ref "R210") (pin "2") (pinfunction "2_2") (pintype "passive"))
      (node (ref "R212") (pin "1") (pinfunction "1_1") (pintype "passive"))
      (node (ref "U202") (pin "6") (pinfunction "FB_6") (pintype "input"))
    )
    (net (code "14") (name "/3V3_PL_PG") (class "Default")
      (node (ref "U202") (pin "4") (pinfunction "PG_4") (pintype "output"))
    )
    (net (code "15") (name "/3V3_PL_SW") (class "Default")
      (node (ref "L202") (pin "1") (pinfunction "1_1") (pintype "passive"))
      (node (ref "U202") (pin "2") (pinfunction "SW_2") (pintype "output"))
    )
    (net (code "16") (name "/3V3_PS_FB") (class "Default")
      (node (ref "C216") (pin "2") (pinfunction "2_2") (pintype "passive"))
      (node (ref "R208") (pin "2") (pinfunction "2_2") (pintype "passive"))
      (node (ref "R211") (pin "1") (pinfunction "1_1") (pintype "passive"))
      (node (ref "U201") (pin "6") (pinfunction "FB_6") (pintype "input"))
    )
    (net (code "17") (name "/3V3_PS_PG") (class "Default")
      (node (ref "U201") (pin "4") (pinfunction "PG_4") (pintype "output"))
    )
    (net (code "18") (name "/3V3_PS_SW") (class "Default")
      (node (ref "L201") (pin "1") (pinfunction "1_1") (pintype "passive"))
      (node (ref "U201") (pin "2") (pinfunction "SW_2") (pintype "output"))
    )
    (net (code "19") (name "/5V_EN") (class "Default")
      (node (ref "R201") (pin "2") (pinfunction "2_2") (pintype "passive"))
      (node (ref "TP200") (pin "1") (pinfunction "1_1") (pintype "passive"))
      (node (ref "U200") (pin "11") (pinfunction "EN_11") (pintype "input"))
    )
    (net (code "20") (name "/5V_EN_R") (class "Default")
      (node (ref "R200") (pin "2") (pinfunction "2_2") (pintype "passive"))
      (node (ref "R201") (pin "1") (pinfunction "1_1") (pintype "passive"))
      (node (ref "R203") (pin "1") (pinfunction "1_1") (pintype "passive"))
      (node (ref "R205") (pin "1") (pinfunction "1_1") (pintype "passive"))
    )
    (net (code "21") (name "/5V_FB") (class "Default")
      (node (ref "C201") (pin "2") (pinfunction "2_2") (pintype "passive"))
      (node (ref "R202") (pin "2") (pinfunction "2_2") (pintype "passive"))
      (node (ref "R204") (pin "1") (pinfunction "1_1") (pintype "passive"))
      (node (ref "U200") (pin "4") (pinfunction "FB_4") (pintype "input"))
    )
    (net (code "22") (name "/5V_MODE") (class "Default")
      (node (ref "R203") (pin "2") (pinfunction "2_2") (pintype "passive"))
      (node (ref "TP201") (pin "1") (pinfunction "1_1") (pintype "passive"))
      (node (ref "U200") (pin "12") (pinfunction "MODE_12") (pintype "input"))
    )
    (net (code "23") (name "/5V_PG") (class "Default")
      (node (ref "R206") (pin "2") (pinfunction "2_2") (pintype "passive"))
      (node (ref "TP204") (pin "1") (pinfunction "1_1") (pintype "passive"))
      (node (ref "U200") (pin "3") (pinfunction "PG_3") (pintype "output"))
    )
    (net (code "24") (name "/5V_SW") (class "Default")
      (node (ref "C200") (pin "2") (pinfunction "2_2") (pintype "passive"))
      (node (ref "L200") (pin "1") (pinfunction "1_1") (pintype "passive"))
      (node (ref "U200") (pin "7") (pinfunction "SW_7") (pintype "output"))
    )
    (net (code "25") (name "/EN_1V8PL") (class "Default")
      (node (ref "R217") (pin "2") (pinfunction "2_2") (pintype "passive"))
      (node (ref "U204") (pin "4") (pinfunction "EN_4") (pintype "input"))
    )
    (net (code "26") (name "/EN_1V8PS") (class "Default")
      (node (ref "R215") (pin "2") (pinfunction "2_2") (pintype "passive"))
      (node (ref "U203") (pin "4") (pinfunction "EN_4") (pintype "input"))
    )
    (net (code "27") (name "/EN_3V3PL") (class "Default")
      (node (ref "R209") (pin "2") (pinfunction "2_2") (pintype "passive"))
      (node (ref "U202") (pin "5") (pinfunction "EN_5") (pintype "input"))
    )
    (net (code "28") (name "/EN_3V3PS") (class "Default")
      (node (ref "R207") (pin "2") (pinfunction "2_2") (pintype "passive"))
      (node (ref "U201") (pin "5") (pinfunction "EN_5") (pintype "input"))
    )
    (net (code "29") (name "/EN_PL") (class "Default")
      (node (ref "R209") (pin "1") (pinfunction "1_1") (pintype "passive"))
      (node (ref "R217") (pin "1") (pinfunction "1_1") (pintype "passive"))
      (node (ref "TP203") (pin "1") (pinfunction "1_1") (pintype "passive"))
    )
    (net (code "30") (name "/EN_PS") (class "Default")
      (node (ref "R207") (pin "1") (pinfunction "1_1") (pintype "passive"))
      (node (ref "R215") (pin "1") (pinfunction "1_1") (pintype "passive"))
      (node (ref "TP202") (pin "1") (pinfunction "1_1") (pintype "passive"))
    )
    (net (code "31") (name "/TPS_VCC") (class "Default")
      (node (ref "C214") (pin "1") (pinfunction "1_1") (pintype "passive"))
      (node (ref "R206") (pin "1") (pinfunction "1_1") (pintype "passive"))
      (node (ref "U200") (pin "9") (pinfunction "VCC_9") (pintype "output"))
    )
    (net (code "32") (name "GND") (class "Default")
      (node (ref "C202") (pin "2") (pinfunction "2_2") (pintype "passive"))
      (node (ref "C203") (pin "2") (pinfunction "2_2") (pintype "passive"))
      (node (ref "C204") (pin "2") (pinfunction "2_2") (pintype "passive"))
      (node (ref "C205") (pin "2") (pinfunction "2_2") (pintype "passive"))
      (node (ref "C206") (pin "2") (pinfunction "2_2") (pintype "passive"))
      (node (ref "C207") (pin "2") (pinfunction "2_2") (pintype "passive"))
      (node (ref "C208") (pin "2") (pinfunction "2_2") (pintype "passive"))
      (node (ref "C209") (pin "2") (pinfunction "2_2") (pintype "passive"))
      (node (ref "C210") (pin "2") (pinfunction "2_2") (pintype "passive"))
      (node (ref "C211") (pin "2") (pinfunction "2_2") (pintype "passive"))
      (node (ref "C212") (pin "2") (pinfunction "2_2") (pintype "passive"))
      (node (ref "C213") (pin "2") (pinfunction "2_2") (pintype "passive"))
      (node (ref "C214") (pin "2") (pinfunction "2_2") (pintype "passive"))
      (node (ref "C215") (pin "2") (pinfunction "2_2") (pintype "passive"))
      (node (ref "C218") (pin "2") (pinfunction "2_2") (pintype "passive"))
      (node (ref "C219") (pin "2") (pinfunction "2_2") (pintype "passive"))
      (node (ref "C220") (pin "2") (pinfunction "2_2") (pintype "passive"))
      (node (ref "C221") (pin "2") (pinfunction "2_2") (pintype "passive"))
      (node (ref "C222") (pin "2") (pinfunction "2_2") (pintype "passive"))
      (node (ref "C223") (pin "2") (pinfunction "2_2") (pintype "passive"))
      (node (ref "C224") (pin "2") (pinfunction "2_2") (pintype "passive"))
      (node (ref "C225") (pin "2") (pinfunction "2_2") (pintype "passive"))
      (node (ref "C226") (pin "2") (pinfunction "2_2") (pintype "passive"))
      (node (ref "C227") (pin "2") (pinfunction "2_2") (pintype "passive"))
      (node (ref "C230") (pin "2") (pinfunction "2_2") (pintype "passive"))
      (node (ref "C231") (pin "2") (pinfunction "2_2") (pintype "passive"))
      (node (ref "C232") (pin "2") (pinfunction "2_2") (pintype "passive"))
      (node (ref "C233") (pin "2") (pinfunction "2_2") (pintype "passive"))
      (node (ref "C234") (pin "2") (pinfunction "2_2") (pintype "passive"))
      (node (ref "C235") (pin "2") (pinfunction "2_2") (pintype "passive"))
      (node (ref "C236") (pin "2") (pinfunction "2_2") (pintype "passive"))
      (node (ref "C237") (pin "2") (pinfunction "2_2") (pintype "passive"))
      (node (ref "C238") (pin "2") (pinfunction "2_2") (pintype "passive"))
      (node (ref "C239") (pin "2") (pinfunction "2_2") (pintype "passive"))
      (node (ref "C240") (pin "2") (pinfunction "2_2") (pintype "passive"))
      (node (ref "C241") (pin "2") (pinfunction "2_2") (pintype "passive"))
      (node (ref "R204") (pin "2") (pinfunction "2_2") (pintype "passive"))
      (node (ref "R205") (pin "2") (pinfunction "2_2") (pintype "passive"))
      (node (ref "R211") (pin "2") (pinfunction "2_2") (pintype "passive"))
      (node (ref "R212") (pin "2") (pinfunction "2_2") (pintype "passive"))
      (node (ref "R219") (pin "2") (pinfunction "2_2") (pintype "passive"))
      (node (ref "R220") (pin "2") (pinfunction "2_2") (pintype "passive"))
      (node (ref "U200") (pin "10") (pinfunction "AGND_10") (pintype "power_in"))
      (node (ref "U200") (pin "2") (pinfunction "PGND_2") (pintype "power_in"))
      (node (ref "U201") (pin "3") (pinfunction "GND_3") (pintype "power_in"))
      (node (ref "U202") (pin "3") (pinfunction "GND_3") (pintype "power_in"))
      (node (ref "U203") (pin "1") (pinfunction "GND_1") (pintype "power_in"))
      (node (ref "U204") (pin "1") (pinfunction "GND_1") (pintype "power_in"))
    )
    (net (code "33") (name "Net-(U200-SS)") (class "Default")
      (node (ref "C215") (pin "1") (pinfunction "1_1") (pintype "passive"))
      (node (ref "U200") (pin "5") (pinfunction "SS_5") (pintype "output"))
    )
    (net (code "34") (name "Net-(U200-VBST)") (class "Default")
      (node (ref "C200") (pin "1") (pinfunction "1_1") (pintype "passive"))
      (node (ref "U200") (pin "8") (pinfunction "VBST_8") (pintype "input"))
    )
    (net (code "35") (name "Net-(U203-VIN)") (class "Default")
      (node (ref "C230") (pin "1") (pinfunction "1_1") (pintype "passive"))
      (node (ref "C231") (pin "1") (pinfunction "1_1") (pintype "passive"))
      (node (ref "R213") (pin "2") (pinfunction "2_2") (pintype "passive"))
      (node (ref "U203") (pin "3") (pinfunction "VIN_3") (pintype "power_in"))
    )
    (net (code "36") (name "Net-(U204-VIN)") (class "Default")
      (node (ref "C232") (pin "1") (pinfunction "1_1") (pintype "passive"))
      (node (ref "C233") (pin "1") (pinfunction "1_1") (pintype "passive"))
      (node (ref "R214") (pin "2") (pinfunction "2_2") (pintype "passive"))
      (node (ref "U204") (pin "3") (pinfunction "VIN_3") (pintype "power_in"))
    )
    (net (code "37") (name "unconnected-(U200-NC-Pad6)") (class "Default")
      (node (ref "U200") (pin "6") (pinfunction "NC_6") (pintype "passive+no_connect"))
    )
  )
)
